# 780-00029_rev3_Pg3_Backplane_Instrument_.net
KiCad netlist of a schematic drawn in Altium Designer
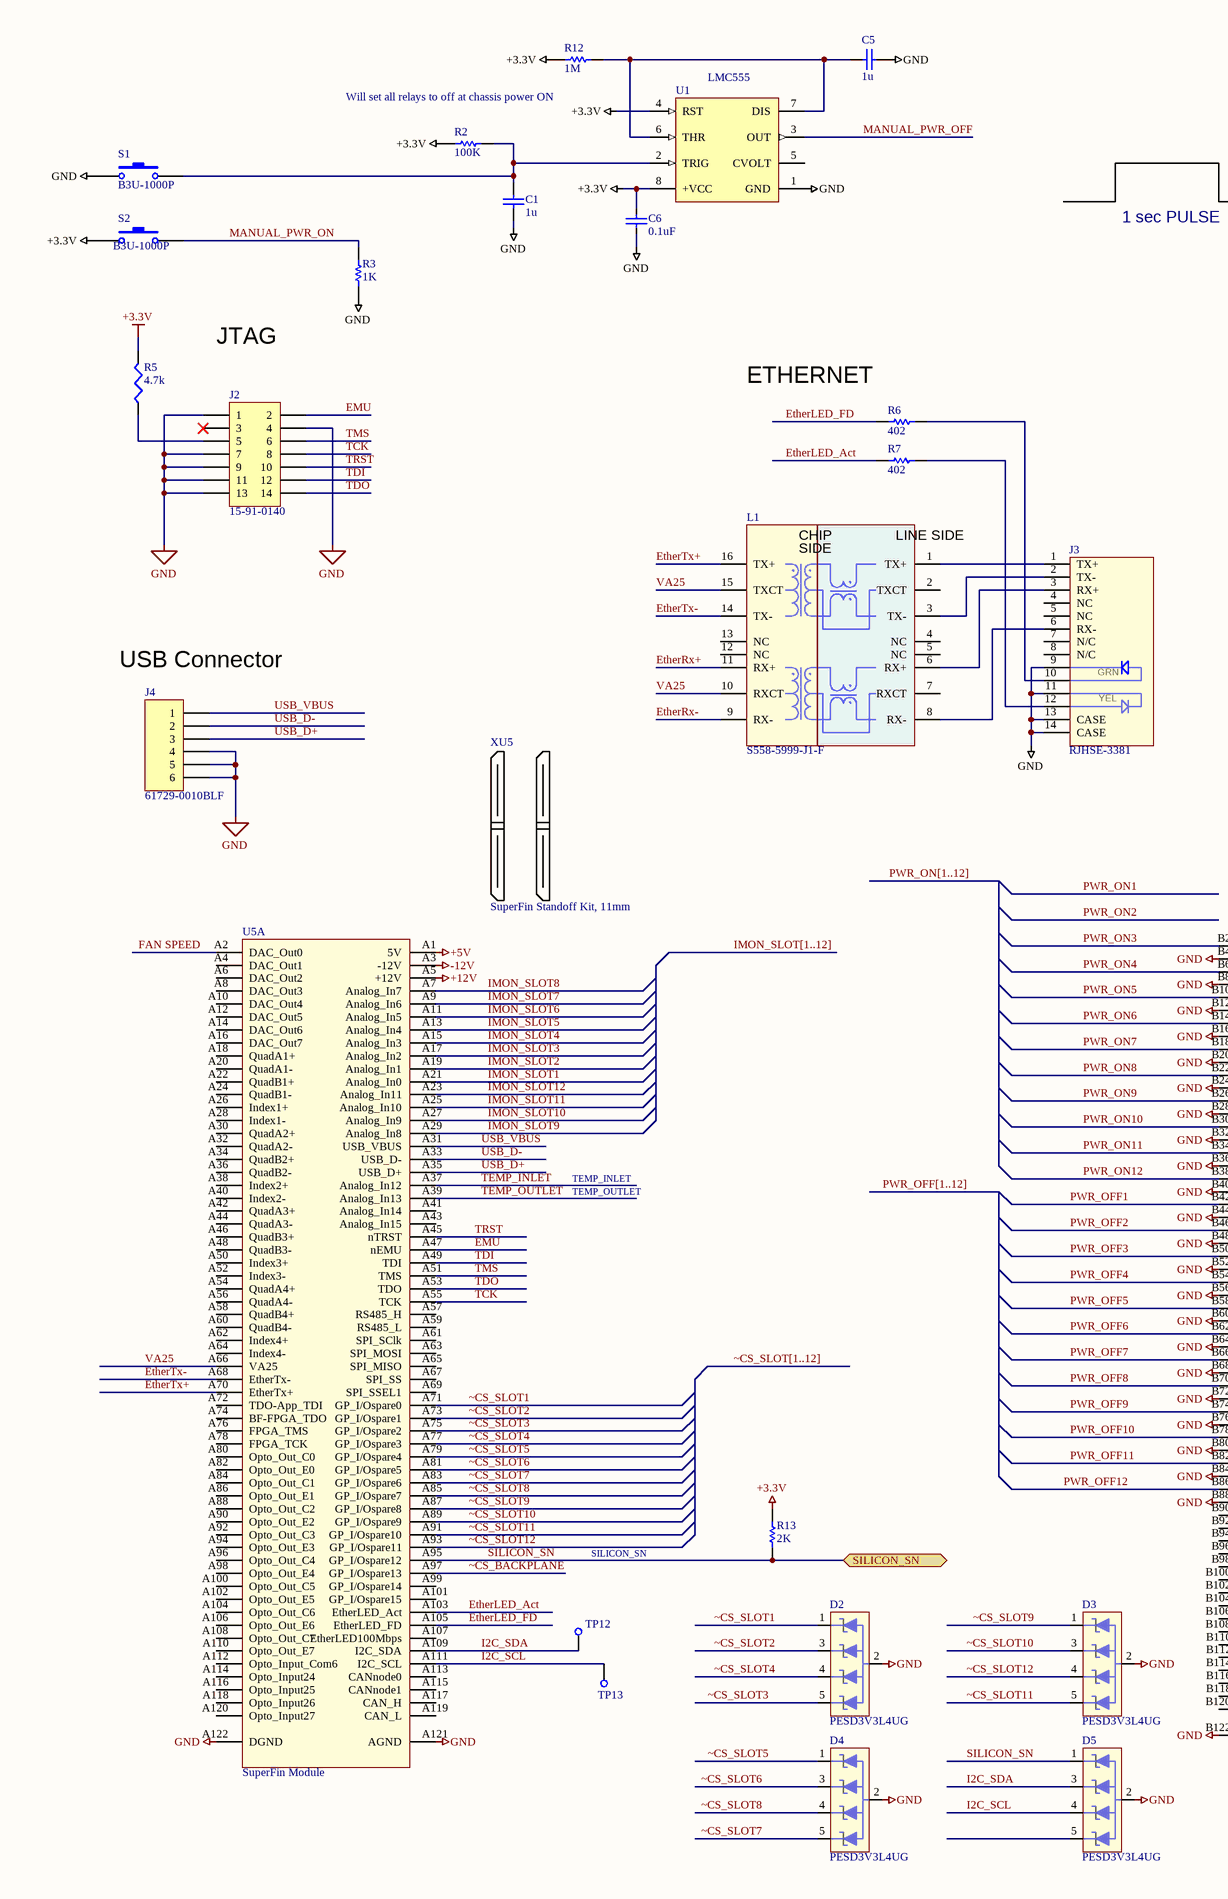
[diagram p0: 780-00029,rev3,Pg3,Backplane, Instrument Crate.SchDoc, left]
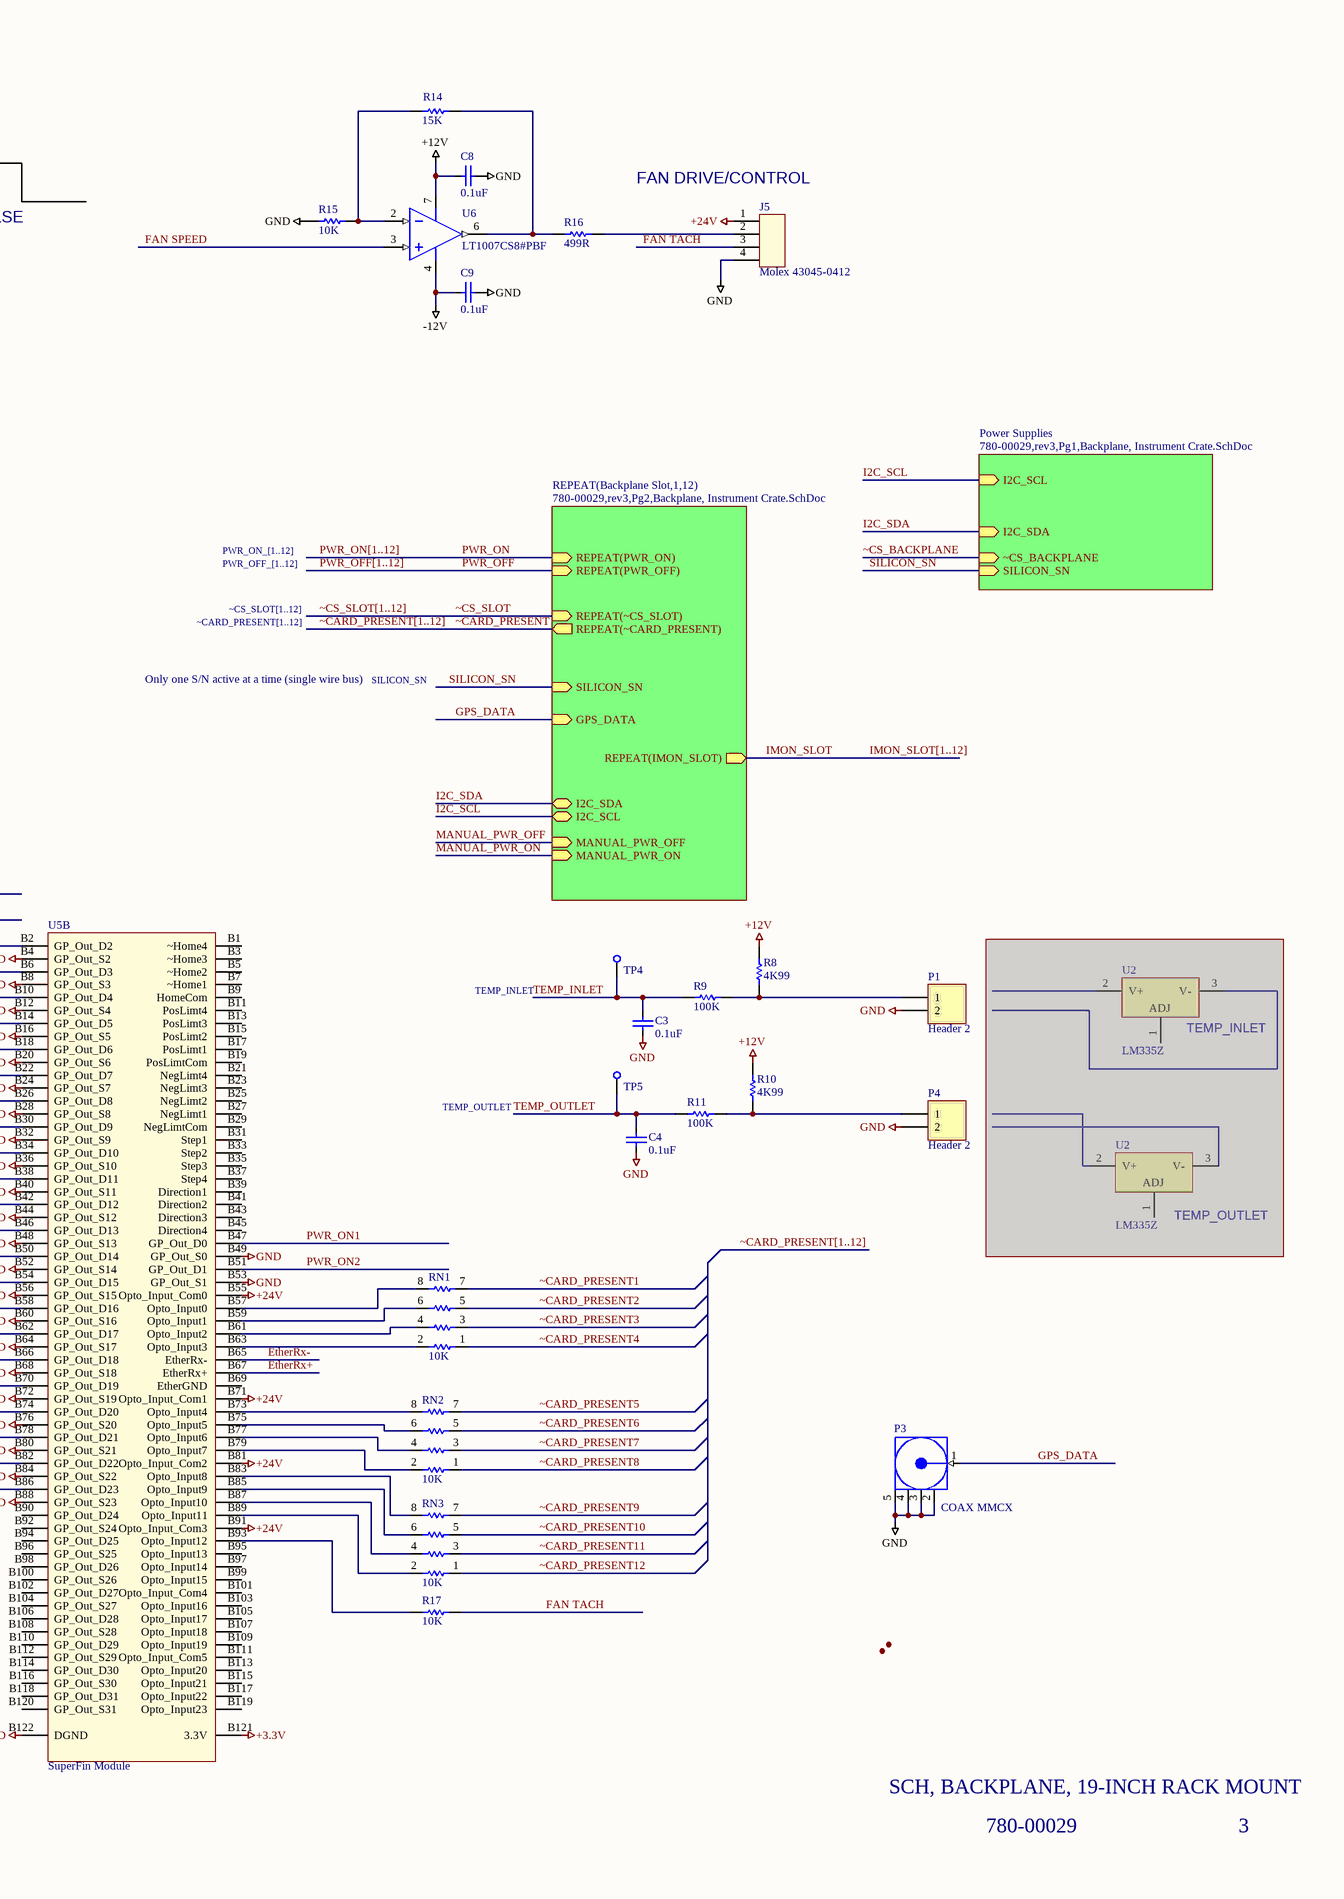
[diagram p1: 780-00029,rev3,Pg3,Backplane, Instrument Crate.SchDoc, right]

(export (version "E")
  (design (tool "Eeschema 10.0.6"))
  (components
    (comp (ref "C1")
      (value "1u")
      (footprint "2012[0805]")
      (description "Capacitor")
      (fields (field (name "MANUFACTURER") "Taiyo Yuden"))
      (libsource (lib "Miscellaneous Devices") (part "Cap"))
    )
    (comp (ref "C3")
      (value "0.1uF")
      (footprint "SMD_0805")
      (description "Capacitor")
      (fields (field (name "Comment") "Cap SMD"))
      (libsource (lib "Richs Schematic Components") (part "Cap SMD"))
    )
    (comp (ref "C4")
      (value "0.1uF")
      (footprint "SMD_0805")
      (description "Capacitor")
      (fields (field (name "Comment") "Cap SMD"))
      (libsource (lib "Richs Schematic Components") (part "Cap SMD"))
    )
    (comp (ref "C5")
      (value "1u")
      (footprint "SMD_0805")
      (description "Capacitor")
      (fields (field (name "MANUFACTURER") "Taiyo Yuden"))
      (libsource (lib "Miscellaneous Devices") (part "Cap"))
    )
    (comp (ref "C6")
      (value "0.1uF")
      (footprint "SMD_0805")
      (description "Capacitor")
      (fields (field (name "Comment") "Cap SMD"))
      (libsource (lib "Richs Schematic Components") (part "Cap SMD"))
    )
    (comp (ref "C8")
      (value "0.1uF")
      (footprint "SMD_0805")
      (description "Capacitor")
      (fields (field (name "Comment") "Cap SMD"))
      (libsource (lib "Richs Schematic Components") (part "Cap SMD"))
    )
    (comp (ref "C9")
      (value "0.1uF")
      (footprint "SMD_0805")
      (description "Capacitor")
      (fields (field (name "Comment") "Cap SMD"))
      (libsource (lib "Richs Schematic Components") (part "Cap SMD"))
    )
    (comp (ref "D2")
      (value "PESD3V3L4UG")
      (footprint "SOT-353")
      (description "Quad ESD Diode 3.3V")
      (fields (field (name "MANUFACTURER") "NXP"))
      (libsource (lib "Richs Schematic Components") (part "ESD Diode 3.3V Quad"))
    )
    (comp (ref "D3")
      (value "PESD3V3L4UG")
      (footprint "SOT-353")
      (description "Quad ESD Diode 3.3V")
      (fields (field (name "MANUFACTURER") "NXP"))
      (libsource (lib "Richs Schematic Components") (part "ESD Diode 3.3V Quad"))
    )
    (comp (ref "D4")
      (value "PESD3V3L4UG")
      (footprint "SOT-353")
      (description "Quad ESD Diode 3.3V")
      (fields (field (name "MANUFACTURER") "NXP"))
      (libsource (lib "Richs Schematic Components") (part "ESD Diode 3.3V Quad"))
    )
    (comp (ref "D5")
      (value "PESD3V3L4UG")
      (footprint "SOT-353")
      (description "Quad ESD Diode 3.3V")
      (fields (field (name "MANUFACTURER") "NXP"))
      (libsource (lib "Richs Schematic Components") (part "ESD Diode 3.3V Quad"))
    )
    (comp (ref "J2")
      (value "15-91-0140")
      (footprint "HDR2X7")
      (description "Header, 7-Pin, Dual row")
      (fields (field (name "MANUFACTURER") "Molex/Waldom"))
      (libsource (lib "Miscellaneous Connectors") (part "Header 7X2"))
    )
    (comp (ref "J3")
      (value "RJHSE-3381")
      (footprint "RJ45, VERT MOUNT, NO MAGNETICS")
      (description "Vertical PC mount, w/o magnetics")
      (libsource (lib "Richs Schematic Components") (part "CONN RJ-45 w/o magnetics"))
    )
    (comp (ref "J4")
      (value "61729-0010BLF")
      (footprint "USB Vertical PCB")
      (description "Header, 6-Pin")
      (fields (field (name "MANUFACTURER") "FCI"))
      (libsource (lib "Miscellaneous Connectors") (part "Header 6"))
    )
    (comp (ref "J5")
      (value "Molex 43045-0412")
      (footprint "CONN Molex Micro-fit, 4 POS")
      (description "Molex Micro Fit 3, Vert PC mount")
      (fields (field (name "MANUFACTURER") "Molex"))
      (libsource (lib "Richs Schematic Components") (part "CONN 4 pin 3mm"))
    )
    (comp (ref "L1")
      (value "S558-5999-J1-F")
      (footprint "10/100BT Magetics module")
      (description "10/100BT Magnetics Module")
      (libsource (lib "Richs Schematic Components") (part "Ethernet Magnetics module"))
    )
    (comp (ref "P1")
      (value "Header 2")
      (footprint "HDR1X2 for IDC")
      (description "Header, 2-Pin")
      (fields (field (name "MANUFACTURER") "TE Connectivity"))
      (libsource (lib "Richs Schematic Components") (part "Header 2"))
    )
    (comp (ref "P3")
      (value "COAX MMCX")
      (footprint "Miscellaneous Connectors:MMCX2.54-V5")
      (description "RF Coaxial PCB Connector, MMCX; Thru-Hole, Vertical Mount Plug,  50 Ohm Impedance")
      (fields (field (name "MANUFACTURER") "Emerson"))
      (libsource (lib "Richs Schematic Components") (part "COAX-M"))
    )
    (comp (ref "P4")
      (value "Header 2")
      (footprint "HDR1X2 for IDC")
      (description "Header, 2-Pin")
      (fields (field (name "MANUFACTURER") "TE Connectivity"))
      (libsource (lib "Richs Schematic Components") (part "Header 2"))
    )
    (comp (ref "R2")
      (value "100K")
      (footprint "SMD_0805")
      (description "Resistor 0805")
      (fields (field (name "MANUFACTURER") "Vishay/Dale") (field (name "Comment") "Res 0805"))
      (libsource (lib "Richs Schematic Components") (part "Res SMD"))
    )
    (comp (ref "R3")
      (value "1K")
      (footprint "SMD_0805")
      (description "Resistor 0805")
      (fields (field (name "MANUFACTURER") "Vishay/Dale") (field (name "Comment") "Res 0805"))
      (libsource (lib "Richs Schematic Components") (part "Res SMD"))
    )
    (comp (ref "R5")
      (value "4.7k")
      (footprint "2012[0805]")
      (description "Resistor")
      (fields (field (name "MANUFACTURER") "Dale/Vishay"))
      (libsource (lib "Miscellaneous Devices") (part "Res3"))
    )
    (comp (ref "R6")
      (value "402")
      (footprint "SMD_0805")
      (description "Resistor 0805")
      (fields (field (name "MANUFACTURER") "Vishay/Dale") (field (name "Comment") "Res 0805"))
      (libsource (lib "Richs Schematic Components") (part "Res SMD"))
    )
    (comp (ref "R7")
      (value "402")
      (footprint "SMD_0805")
      (description "Resistor 0805")
      (fields (field (name "MANUFACTURER") "Vishay/Dale") (field (name "Comment") "Res 0805"))
      (libsource (lib "Richs Schematic Components") (part "Res SMD"))
    )
    (comp (ref "R8")
      (value "4K99")
      (footprint "SMD_0805")
      (description "Resistor 0805")
      (fields (field (name "MANUFACTURER") "Vishay/Dale") (field (name "Comment") "Res 0805"))
      (libsource (lib "Richs Schematic Components") (part "Res SMD"))
    )
    (comp (ref "R9")
      (value "100K")
      (footprint "SMD_0805")
      (description "Resistor 0805")
      (fields (field (name "MANUFACTURER") "Vishay/Dale") (field (name "Comment") "Res 0805"))
      (libsource (lib "Richs Schematic Components") (part "Res SMD"))
    )
    (comp (ref "R10")
      (value "4K99")
      (footprint "SMD_0805")
      (description "Resistor 0805")
      (fields (field (name "MANUFACTURER") "Vishay/Dale") (field (name "Comment") "Res 0805"))
      (libsource (lib "Richs Schematic Components") (part "Res SMD"))
    )
    (comp (ref "R11")
      (value "100K")
      (footprint "SMD_0805")
      (description "Resistor 0805")
      (fields (field (name "MANUFACTURER") "Vishay/Dale") (field (name "Comment") "Res 0805"))
      (libsource (lib "Richs Schematic Components") (part "Res SMD"))
    )
    (comp (ref "R12")
      (value "1M")
      (footprint "SMD_0805")
      (description "Resistor 0805")
      (fields (field (name "MANUFACTURER") "Vishay/Dale") (field (name "Comment") "Res 0805"))
      (libsource (lib "Richs Schematic Components") (part "Res SMD"))
    )
    (comp (ref "R13")
      (value "2K")
      (footprint "SMD_0805")
      (description "Resistor 0805")
      (fields (field (name "MANUFACTURER") "Vishay/Dale") (field (name "Comment") "Res 0805"))
      (libsource (lib "Richs Schematic Components") (part "Res SMD"))
    )
    (comp (ref "R14")
      (value "15K")
      (footprint "SMD_0805")
      (description "Resistor 0805")
      (fields (field (name "MANUFACTURER") "Vishay/Dale") (field (name "Comment") "Res 0805"))
      (libsource (lib "Richs Schematic Components") (part "Res SMD"))
    )
    (comp (ref "R15")
      (value "10K")
      (footprint "SMD_0805")
      (description "Resistor 0805")
      (fields (field (name "MANUFACTURER") "Vishay/Dale") (field (name "Comment") "Res 0805"))
      (libsource (lib "Richs Schematic Components") (part "Res SMD"))
    )
    (comp (ref "R16")
      (value "499R")
      (footprint "SMD_0805")
      (description "Resistor 0805")
      (fields (field (name "MANUFACTURER") "Vishay/Dale") (field (name "Comment") "Res 0805"))
      (libsource (lib "Richs Schematic Components") (part "Res SMD"))
    )
    (comp (ref "R17")
      (value "10K")
      (footprint "SMD_0805")
      (description "Resistor 0805")
      (fields (field (name "MANUFACTURER") "Vishay/Dale") (field (name "Comment") "Res 0805"))
      (libsource (lib "Richs Schematic Components") (part "Res SMD"))
    )
    (comp (ref "RN1")
      (value "10K")
      (footprint "RES ARRAY 0603 x 4")
      (description "Resistor Array 4 Isolated")
      (fields (field (name "MANUFACTURER") "PANASONIC - ECG") (field (name "Comment") "RES ARRAY  x4 10K"))
      (libsource (lib "Richs Schematic Components") (part "RES ARRAY  x4 10K"))
    )
    (comp (ref "RN2")
      (value "10K")
      (footprint "RES ARRAY 0603 x 4")
      (description "Resistor Array 4 Isolated")
      (fields (field (name "MANUFACTURER") "PANASONIC - ECG") (field (name "Comment") "RES ARRAY  x4 10K"))
      (libsource (lib "Richs Schematic Components") (part "RES ARRAY  x4 10K"))
    )
    (comp (ref "RN3")
      (value "10K")
      (footprint "RES ARRAY 0603 x 4")
      (description "Resistor Array 4 Isolated")
      (fields (field (name "MANUFACTURER") "PANASONIC - ECG") (field (name "Comment") "RES ARRAY  x4 10K"))
      (libsource (lib "Richs Schematic Components") (part "RES ARRAY  x4 10K"))
    )
    (comp (ref "S1")
      (value "B3U-1000P")
      (footprint "B3U-1000P")
      (description "Switch")
      (fields (field (name "MANUFACTURER") "Omron Electronics"))
      (libsource (lib "Miscellaneous Devices") (part "SW-PB"))
    )
    (comp (ref "S2")
      (value "B3U-1000P")
      (footprint "B3U-1000P")
      (description "Switch")
      (fields (field (name "MANUFACTURER") "Omron Electronics"))
      (libsource (lib "Miscellaneous Devices") (part "SW-PB"))
    )
    (comp (ref "TP4")
      (value "Test Point SMD")
      (footprint "SMD_TEST POINT")
      (description "SMD loop test point")
      (libsource (lib "Richs Schematic Components") (part "Test Point SMD"))
    )
    (comp (ref "TP5")
      (value "Test Point SMD")
      (footprint "SMD_TEST POINT")
      (description "SMD loop test point")
      (libsource (lib "Richs Schematic Components") (part "Test Point SMD"))
    )
    (comp (ref "TP12")
      (value "Test Point SMD")
      (footprint "SMD_TEST POINT")
      (description "SMD loop test point")
      (libsource (lib "Richs Schematic Components") (part "Test Point SMD"))
    )
    (comp (ref "TP13")
      (value "Test Point SMD")
      (footprint "SMD_TEST POINT")
      (description "SMD loop test point")
      (libsource (lib "Richs Schematic Components") (part "Test Point SMD"))
    )
    (comp (ref "U1")
      (value "LMC555")
      (footprint "M08A_M")
      (description "Timer")
      (fields (field (name "MANUFACTURER") "National Semiconductor") (field (name "Comment") "LM555CMX"))
      (libsource (lib "NSC Analog") (part "LM555CMX"))
    )
    (comp (ref "U2")
      (value "LM335Z")
      (footprint "Z03A")
      (description "Precision Temperature Sensor")
      (fields (field (name "MANUFACTURER") "National Semiconductor"))
      (libsource (lib "NSC Temperature Sensor") (part "LM335Z"))
    )
    (comp (ref "U5")
      (value "SuperFin Module")
      (footprint "SuperFin Footprint")
      (libsource (lib "Richs Schematic Components") (part "SuperFin Module"))
    )
    (comp (ref "U6")
      (value "LT1007CS8#PBF")
      (footprint "S8_M")
      (description "Low Noise BJT input opamp")
      (fields (field (name "MANUFACTURER") "Linear Tech"))
      (libsource (lib "Richs Schematic Components") (part "LT1007CS8#PBF"))
    )
    (comp (ref "XU5")
      (value "SuperFin Standoff Kit, 11mm")
      (libsource (lib "Richs Schematic Components") (part "SuperFin Standoff Kit, 11mm"))
    )
  )
  (nets
    (net (code "1") (name "+3.3V") (class "Default")
      (node (ref "C6") (pin "2") (pinfunction "2_2") (pintype "passive"))
      (node (ref "R12") (pin "1") (pinfunction "1_1") (pintype "passive"))
      (node (ref "R13") (pin "2") (pinfunction "2_2") (pintype "passive"))
      (node (ref "R2") (pin "2") (pinfunction "2_2") (pintype "passive"))
      (node (ref "R5") (pin "2") (pinfunction "2_2") (pintype "passive"))
      (node (ref "S2") (pin "1") (pinfunction "1_1") (pintype "passive"))
      (node (ref "U1") (pin "4") (pinfunction "RST_4") (pintype "input"))
      (node (ref "U1") (pin "8") (pinfunction "+VCC_8") (pintype "power_in"))
      (node (ref "U5") (pin "B121") (pinfunction "3.3V_B121") (pintype "passive"))
    )
    (net (code "2") (name "+5V") (class "Default")
      (node (ref "U5") (pin "A1") (pinfunction "5V_A1") (pintype "passive"))
    )
    (net (code "3") (name "+12V") (class "Default")
      (node (ref "C8") (pin "1") (pinfunction "1_1") (pintype "passive"))
      (node (ref "R10") (pin "2") (pinfunction "2_2") (pintype "passive"))
      (node (ref "R8") (pin "2") (pinfunction "2_2") (pintype "passive"))
      (node (ref "U5") (pin "A5") (pinfunction "+12V_A5") (pintype "passive"))
      (node (ref "U6") (pin "7") (pinfunction "V+_7") (pintype "power_in"))
    )
    (net (code "4") (name "+24V") (class "Default")
      (node (ref "J5") (pin "1") (pintype "passive"))
      (node (ref "U5") (pin "B55") (pinfunction "Opto_Input_Com0_B55") (pintype "passive"))
      (node (ref "U5") (pin "B71") (pinfunction "Opto_Input_Com1_B71") (pintype "passive"))
      (node (ref "U5") (pin "B81") (pinfunction "Opto_Input_Com2_B81") (pintype "passive"))
      (node (ref "U5") (pin "B91") (pinfunction "Opto_Input_Com3_B91") (pintype "passive"))
    )
    (net (code "5") (name "-12V") (class "Default")
      (node (ref "C9") (pin "1") (pinfunction "1_1") (pintype "passive"))
      (node (ref "U5") (pin "A3") (pinfunction "-12V_A3") (pintype "passive"))
      (node (ref "U6") (pin "4") (pinfunction "V-_4") (pintype "power_in"))
    )
    (net (code "6") (name "/EMU") (class "Default")
      (node (ref "J2") (pin "2") (pinfunction "2_2") (pintype "passive"))
      (node (ref "U5") (pin "A47") (pinfunction "nEMU_A47") (pintype "passive"))
    )
    (net (code "7") (name "/EtherLED_Act") (class "Default")
      (node (ref "R7") (pin "1") (pinfunction "1_1") (pintype "passive"))
      (node (ref "U5") (pin "A103") (pinfunction "EtherLED_Act_A103") (pintype "passive"))
    )
    (net (code "8") (name "/EtherLED_FD") (class "Default")
      (node (ref "R6") (pin "1") (pinfunction "1_1") (pintype "passive"))
      (node (ref "U5") (pin "A105") (pinfunction "EtherLED_FD_A105") (pintype "passive"))
    )
    (net (code "9") (name "/EtherRx+") (class "Default")
      (node (ref "L1") (pin "11") (pinfunction "RX+_11") (pintype "passive"))
      (node (ref "U5") (pin "B67") (pinfunction "EtherRx+_B67") (pintype "passive"))
    )
    (net (code "10") (name "/EtherRx-") (class "Default")
      (node (ref "L1") (pin "9") (pinfunction "RX-_9") (pintype "passive"))
      (node (ref "U5") (pin "B65") (pinfunction "EtherRx-_B65") (pintype "passive"))
    )
    (net (code "11") (name "/EtherTx+") (class "Default")
      (node (ref "L1") (pin "16") (pinfunction "TX+_16") (pintype "passive"))
      (node (ref "U5") (pin "A70") (pinfunction "EtherTx+_A70") (pintype "passive"))
    )
    (net (code "12") (name "/EtherTx-") (class "Default")
      (node (ref "L1") (pin "14") (pinfunction "TX-_14") (pintype "passive"))
      (node (ref "U5") (pin "A68") (pinfunction "EtherTx-_A68") (pintype "passive"))
    )
    (net (code "13") (name "/FAN SPEED") (class "Default")
      (node (ref "U5") (pin "A2") (pinfunction "DAC_Out0_A2") (pintype "passive"))
      (node (ref "U6") (pin "3") (pinfunction "IN+_3") (pintype "input"))
    )
    (net (code "14") (name "/FAN TACH") (class "Default")
      (node (ref "J5") (pin "3") (pintype "passive"))
      (node (ref "R17") (pin "2") (pinfunction "2_2") (pintype "passive"))
    )
    (net (code "15") (name "/GPS_DATA") (class "Default")
      (node (ref "P3") (pin "1") (pinfunction "Signal_1") (pintype "input"))
    )
    (net (code "16") (name "/I2C_SCL") (class "Default")
      (node (ref "D5") (pin "4") (pintype "passive"))
      (node (ref "TP13") (pin "1") (pinfunction "TP_1") (pintype "passive"))
      (node (ref "U5") (pin "A111") (pinfunction "I2C_SCL_A111") (pintype "passive"))
    )
    (net (code "17") (name "/I2C_SDA") (class "Default")
      (node (ref "D5") (pin "3") (pintype "passive"))
      (node (ref "TP12") (pin "1") (pinfunction "TP_1") (pintype "passive"))
      (node (ref "U5") (pin "A109") (pinfunction "I2C_SDA_A109") (pintype "passive"))
    )
    (net (code "19") (name "/IMON_SLOT1") (class "Default")
      (node (ref "U5") (pin "A21") (pinfunction "Analog_In0_A21") (pintype "passive"))
    )
    (net (code "20") (name "/IMON_SLOT2") (class "Default")
      (node (ref "U5") (pin "A19") (pinfunction "Analog_In1_A19") (pintype "passive"))
    )
    (net (code "21") (name "/IMON_SLOT3") (class "Default")
      (node (ref "U5") (pin "A17") (pinfunction "Analog_In2_A17") (pintype "passive"))
    )
    (net (code "22") (name "/IMON_SLOT4") (class "Default")
      (node (ref "U5") (pin "A15") (pinfunction "Analog_In3_A15") (pintype "passive"))
    )
    (net (code "23") (name "/IMON_SLOT5") (class "Default")
      (node (ref "U5") (pin "A13") (pinfunction "Analog_In4_A13") (pintype "passive"))
    )
    (net (code "24") (name "/IMON_SLOT6") (class "Default")
      (node (ref "U5") (pin "A11") (pinfunction "Analog_In5_A11") (pintype "passive"))
    )
    (net (code "25") (name "/IMON_SLOT7") (class "Default")
      (node (ref "U5") (pin "A9") (pinfunction "Analog_In6_A9") (pintype "passive"))
    )
    (net (code "26") (name "/IMON_SLOT8") (class "Default")
      (node (ref "U5") (pin "A7") (pinfunction "Analog_In7_A7") (pintype "passive"))
    )
    (net (code "27") (name "/IMON_SLOT9") (class "Default")
      (node (ref "U5") (pin "A29") (pinfunction "Analog_In8_A29") (pintype "passive"))
    )
    (net (code "28") (name "/IMON_SLOT10") (class "Default")
      (node (ref "U5") (pin "A27") (pinfunction "Analog_In9_A27") (pintype "passive"))
    )
    (net (code "29") (name "/IMON_SLOT11") (class "Default")
      (node (ref "U5") (pin "A25") (pinfunction "Analog_In10_A25") (pintype "passive"))
    )
    (net (code "30") (name "/IMON_SLOT12") (class "Default")
      (node (ref "U5") (pin "A23") (pinfunction "Analog_In11_A23") (pintype "passive"))
    )
    (net (code "32") (name "/MANUAL_PWR_OFF") (class "Default")
      (node (ref "U1") (pin "3") (pinfunction "OUT_3") (pintype "output"))
    )
    (net (code "33") (name "/MANUAL_PWR_ON") (class "Default")
      (node (ref "R3") (pin "2") (pinfunction "2_2") (pintype "passive"))
      (node (ref "S2") (pin "2") (pinfunction "2_2") (pintype "passive"))
    )
    (net (code "35") (name "/PWR_OFF1") (class "Default")
      (node (ref "U5") (pin "B42") (pinfunction "GP_Out_D12_B42") (pintype "passive"))
    )
    (net (code "36") (name "/PWR_OFF2") (class "Default")
      (node (ref "U5") (pin "B46") (pinfunction "GP_Out_D13_B46") (pintype "passive"))
    )
    (net (code "37") (name "/PWR_OFF3") (class "Default")
      (node (ref "U5") (pin "B50") (pinfunction "GP_Out_D14_B50") (pintype "passive"))
    )
    (net (code "38") (name "/PWR_OFF4") (class "Default")
      (node (ref "U5") (pin "B54") (pinfunction "GP_Out_D15_B54") (pintype "passive"))
    )
    (net (code "39") (name "/PWR_OFF5") (class "Default")
      (node (ref "U5") (pin "B58") (pinfunction "GP_Out_D16_B58") (pintype "passive"))
    )
    (net (code "40") (name "/PWR_OFF6") (class "Default")
      (node (ref "U5") (pin "B62") (pinfunction "GP_Out_D17_B62") (pintype "passive"))
    )
    (net (code "41") (name "/PWR_OFF7") (class "Default")
      (node (ref "U5") (pin "B66") (pinfunction "GP_Out_D18_B66") (pintype "passive"))
    )
    (net (code "42") (name "/PWR_OFF8") (class "Default")
      (node (ref "U5") (pin "B70") (pinfunction "GP_Out_D19_B70") (pintype "passive"))
    )
    (net (code "43") (name "/PWR_OFF9") (class "Default")
      (node (ref "U5") (pin "B74") (pinfunction "GP_Out_D20_B74") (pintype "passive"))
    )
    (net (code "44") (name "/PWR_OFF10") (class "Default")
      (node (ref "U5") (pin "B78") (pinfunction "GP_Out_D21_B78") (pintype "passive"))
    )
    (net (code "45") (name "/PWR_OFF11") (class "Default")
      (node (ref "U5") (pin "B82") (pinfunction "GP_Out_D22_B82") (pintype "passive"))
    )
    (net (code "46") (name "/PWR_OFF12") (class "Default")
      (node (ref "U5") (pin "B86") (pinfunction "GP_Out_D23_B86") (pintype "passive"))
    )
    (net (code "49") (name "/PWR_ON1") (class "Default")
      (node (ref "U5") (pin "B47") (pinfunction "GP_Out_D0_B47") (pintype "passive"))
    )
    (net (code "50") (name "/PWR_ON2") (class "Default")
      (node (ref "U5") (pin "B51") (pinfunction "GP_Out_D1_B51") (pintype "passive"))
    )
    (net (code "51") (name "/PWR_ON3") (class "Default")
      (node (ref "U5") (pin "B2") (pinfunction "GP_Out_D2_B2") (pintype "passive"))
    )
    (net (code "52") (name "/PWR_ON4") (class "Default")
      (node (ref "U5") (pin "B6") (pinfunction "GP_Out_D3_B6") (pintype "passive"))
    )
    (net (code "53") (name "/PWR_ON5") (class "Default")
      (node (ref "U5") (pin "B10") (pinfunction "GP_Out_D4_B10") (pintype "passive"))
    )
    (net (code "54") (name "/PWR_ON6") (class "Default")
      (node (ref "U5") (pin "B14") (pinfunction "GP_Out_D5_B14") (pintype "passive"))
    )
    (net (code "55") (name "/PWR_ON7") (class "Default")
      (node (ref "U5") (pin "B18") (pinfunction "GP_Out_D6_B18") (pintype "passive"))
    )
    (net (code "56") (name "/PWR_ON8") (class "Default")
      (node (ref "U5") (pin "B22") (pinfunction "GP_Out_D7_B22") (pintype "passive"))
    )
    (net (code "57") (name "/PWR_ON9") (class "Default")
      (node (ref "U5") (pin "B26") (pinfunction "GP_Out_D8_B26") (pintype "passive"))
    )
    (net (code "58") (name "/PWR_ON10") (class "Default")
      (node (ref "U5") (pin "B30") (pinfunction "GP_Out_D9_B30") (pintype "passive"))
    )
    (net (code "59") (name "/PWR_ON11") (class "Default")
      (node (ref "U5") (pin "B34") (pinfunction "GP_Out_D10_B34") (pintype "passive"))
    )
    (net (code "60") (name "/PWR_ON12") (class "Default")
      (node (ref "U5") (pin "B38") (pinfunction "GP_Out_D11_B38") (pintype "passive"))
    )
    (net (code "62") (name "/SILICON_SN") (class "Default")
      (node (ref "D5") (pin "1") (pintype "passive"))
      (node (ref "R13") (pin "1") (pinfunction "1_1") (pintype "passive"))
      (node (ref "U5") (pin "A95") (pinfunction "GP_I/Ospare12_A95") (pintype "passive"))
    )
    (net (code "63") (name "/TCK") (class "Default")
      (node (ref "J2") (pin "8") (pinfunction "8_8") (pintype "passive"))
      (node (ref "U5") (pin "A55") (pinfunction "TCK_A55") (pintype "passive"))
    )
    (net (code "64") (name "/TDI") (class "Default")
      (node (ref "J2") (pin "12") (pinfunction "12_12") (pintype "passive"))
      (node (ref "U5") (pin "A49") (pinfunction "TDI_A49") (pintype "passive"))
    )
    (net (code "65") (name "/TDO") (class "Default")
      (node (ref "J2") (pin "14") (pinfunction "14_14") (pintype "passive"))
      (node (ref "U5") (pin "A53") (pinfunction "TDO_A53") (pintype "passive"))
    )
    (net (code "66") (name "/TEMP_INLET") (class "Default")
      (node (ref "C3") (pin "2") (pinfunction "2_2") (pintype "passive"))
      (node (ref "R9") (pin "1") (pinfunction "1_1") (pintype "passive"))
      (node (ref "TP4") (pin "1") (pinfunction "TP_1") (pintype "passive"))
      (node (ref "U5") (pin "A37") (pinfunction "Analog_In12_A37") (pintype "passive"))
    )
    (net (code "67") (name "/TEMP_OUTLET") (class "Default")
      (node (ref "C4") (pin "2") (pinfunction "2_2") (pintype "passive"))
      (node (ref "R11") (pin "1") (pinfunction "1_1") (pintype "passive"))
      (node (ref "TP5") (pin "1") (pinfunction "TP_1") (pintype "passive"))
      (node (ref "U5") (pin "A39") (pinfunction "Analog_In13_A39") (pintype "passive"))
    )
    (net (code "68") (name "/TMS") (class "Default")
      (node (ref "J2") (pin "6") (pinfunction "6_6") (pintype "passive"))
      (node (ref "U5") (pin "A51") (pinfunction "TMS_A51") (pintype "passive"))
    )
    (net (code "69") (name "/TRST") (class "Default")
      (node (ref "J2") (pin "10") (pinfunction "10_10") (pintype "passive"))
      (node (ref "U5") (pin "A45") (pinfunction "nTRST_A45") (pintype "passive"))
    )
    (net (code "70") (name "/USB_D+") (class "Default")
      (node (ref "J4") (pin "3") (pinfunction "3_3") (pintype "passive"))
      (node (ref "U5") (pin "A35") (pinfunction "USB_D+_A35") (pintype "passive"))
    )
    (net (code "71") (name "/USB_D-") (class "Default")
      (node (ref "J4") (pin "2") (pinfunction "2_2") (pintype "passive"))
      (node (ref "U5") (pin "A33") (pinfunction "USB_D-_A33") (pintype "passive"))
    )
    (net (code "72") (name "/USB_VBUS") (class "Default")
      (node (ref "J4") (pin "1") (pinfunction "1_1") (pintype "passive"))
      (node (ref "U5") (pin "A31") (pinfunction "USB_VBUS_A31") (pintype "passive"))
    )
    (net (code "73") (name "/VA25") (class "Default")
      (node (ref "L1") (pin "10") (pinfunction "RXCT_10") (pintype "passive"))
      (node (ref "L1") (pin "15") (pinfunction "TXCT_15") (pintype "passive"))
      (node (ref "U5") (pin "A66") (pinfunction "VA25_A66") (pintype "passive"))
    )
    (net (code "75") (name "/~CARD_PRESENT1") (class "Default")
      (node (ref "RN1") (pin "7") (pinfunction "1_7") (pintype "passive"))
    )
    (net (code "76") (name "/~CARD_PRESENT2") (class "Default")
      (node (ref "RN1") (pin "5") (pinfunction "5_5") (pintype "passive"))
    )
    (net (code "77") (name "/~CARD_PRESENT3") (class "Default")
      (node (ref "RN1") (pin "3") (pinfunction "3_3") (pintype "passive"))
    )
    (net (code "78") (name "/~CARD_PRESENT4") (class "Default")
      (node (ref "RN1") (pin "1") (pinfunction "1_1") (pintype "passive"))
    )
    (net (code "79") (name "/~CARD_PRESENT5") (class "Default")
      (node (ref "RN2") (pin "7") (pinfunction "1_7") (pintype "passive"))
    )
    (net (code "80") (name "/~CARD_PRESENT6") (class "Default")
      (node (ref "RN2") (pin "5") (pinfunction "5_5") (pintype "passive"))
    )
    (net (code "81") (name "/~CARD_PRESENT7") (class "Default")
      (node (ref "RN2") (pin "3") (pinfunction "3_3") (pintype "passive"))
    )
    (net (code "82") (name "/~CARD_PRESENT8") (class "Default")
      (node (ref "RN2") (pin "1") (pinfunction "1_1") (pintype "passive"))
    )
    (net (code "83") (name "/~CARD_PRESENT9") (class "Default")
      (node (ref "RN3") (pin "7") (pinfunction "1_7") (pintype "passive"))
    )
    (net (code "84") (name "/~CARD_PRESENT10") (class "Default")
      (node (ref "RN3") (pin "5") (pinfunction "5_5") (pintype "passive"))
    )
    (net (code "85") (name "/~CARD_PRESENT11") (class "Default")
      (node (ref "RN3") (pin "3") (pinfunction "3_3") (pintype "passive"))
    )
    (net (code "86") (name "/~CARD_PRESENT12") (class "Default")
      (node (ref "RN3") (pin "1") (pinfunction "1_1") (pintype "passive"))
    )
    (net (code "88") (name "/~CS_BACKPLANE") (class "Default")
      (node (ref "U5") (pin "A97") (pinfunction "GP_I/Ospare13_A97") (pintype "passive"))
    )
    (net (code "90") (name "/~CS_SLOT1") (class "Default")
      (node (ref "D2") (pin "1") (pintype "passive"))
      (node (ref "U5") (pin "A71") (pinfunction "GP_I/Ospare0_A71") (pintype "passive"))
    )
    (net (code "91") (name "/~CS_SLOT2") (class "Default")
      (node (ref "D2") (pin "3") (pintype "passive"))
      (node (ref "U5") (pin "A73") (pinfunction "GP_I/Ospare1_A73") (pintype "passive"))
    )
    (net (code "92") (name "/~CS_SLOT3") (class "Default")
      (node (ref "D2") (pin "5") (pintype "passive"))
      (node (ref "U5") (pin "A75") (pinfunction "GP_I/Ospare2_A75") (pintype "passive"))
    )
    (net (code "93") (name "/~CS_SLOT4") (class "Default")
      (node (ref "D2") (pin "4") (pintype "passive"))
      (node (ref "U5") (pin "A77") (pinfunction "GP_I/Ospare3_A77") (pintype "passive"))
    )
    (net (code "94") (name "/~CS_SLOT5") (class "Default")
      (node (ref "D4") (pin "1") (pintype "passive"))
      (node (ref "U5") (pin "A79") (pinfunction "GP_I/Ospare4_A79") (pintype "passive"))
    )
    (net (code "95") (name "/~CS_SLOT6") (class "Default")
      (node (ref "D4") (pin "3") (pintype "passive"))
      (node (ref "U5") (pin "A81") (pinfunction "GP_I/Ospare5_A81") (pintype "passive"))
    )
    (net (code "96") (name "/~CS_SLOT7") (class "Default")
      (node (ref "D4") (pin "5") (pintype "passive"))
      (node (ref "U5") (pin "A83") (pinfunction "GP_I/Ospare6_A83") (pintype "passive"))
    )
    (net (code "97") (name "/~CS_SLOT8") (class "Default")
      (node (ref "D4") (pin "4") (pintype "passive"))
      (node (ref "U5") (pin "A85") (pinfunction "GP_I/Ospare7_A85") (pintype "passive"))
    )
    (net (code "98") (name "/~CS_SLOT9") (class "Default")
      (node (ref "D3") (pin "1") (pintype "passive"))
      (node (ref "U5") (pin "A87") (pinfunction "GP_I/Ospare8_A87") (pintype "passive"))
    )
    (net (code "99") (name "/~CS_SLOT10") (class "Default")
      (node (ref "D3") (pin "3") (pintype "passive"))
      (node (ref "U5") (pin "A89") (pinfunction "GP_I/Ospare9_A89") (pintype "passive"))
    )
    (net (code "100") (name "/~CS_SLOT11") (class "Default")
      (node (ref "D3") (pin "5") (pintype "passive"))
      (node (ref "U5") (pin "A91") (pinfunction "GP_I/Ospare10_A91") (pintype "passive"))
    )
    (net (code "101") (name "/~CS_SLOT12") (class "Default")
      (node (ref "D3") (pin "4") (pintype "passive"))
      (node (ref "U5") (pin "A93") (pinfunction "GP_I/Ospare11_A93") (pintype "passive"))
    )
    (net (code "103") (name "GND") (class "Default")
      (node (ref "C1") (pin "1") (pinfunction "1_1") (pintype "passive"))
      (node (ref "C3") (pin "1") (pinfunction "1_1") (pintype "passive"))
      (node (ref "C4") (pin "1") (pinfunction "1_1") (pintype "passive"))
      (node (ref "C5") (pin "2") (pinfunction "2_2") (pintype "passive"))
      (node (ref "C6") (pin "1") (pinfunction "1_1") (pintype "passive"))
      (node (ref "C8") (pin "2") (pinfunction "2_2") (pintype "passive"))
      (node (ref "C9") (pin "2") (pinfunction "2_2") (pintype "passive"))
      (node (ref "D2") (pin "2") (pintype "passive"))
      (node (ref "D3") (pin "2") (pintype "passive"))
      (node (ref "D4") (pin "2") (pintype "passive"))
      (node (ref "D5") (pin "2") (pintype "passive"))
      (node (ref "J2") (pin "1") (pinfunction "1_1") (pintype "passive"))
      (node (ref "J2") (pin "11") (pinfunction "11_11") (pintype "passive"))
      (node (ref "J2") (pin "13") (pinfunction "13_13") (pintype "passive"))
      (node (ref "J2") (pin "4") (pinfunction "4_4") (pintype "passive"))
      (node (ref "J2") (pin "7") (pinfunction "7_7") (pintype "passive"))
      (node (ref "J2") (pin "9") (pinfunction "9_9") (pintype "passive"))
      (node (ref "J3") (pin "11") (pinfunction "YEL-Cathode_11") (pintype "passive"))
      (node (ref "J3") (pin "13") (pinfunction "CASE_13") (pintype "passive"))
      (node (ref "J3") (pin "14") (pinfunction "CASE_14") (pintype "passive"))
      (node (ref "J3") (pin "9") (pinfunction "GRN-Anode_9") (pintype "passive"))
      (node (ref "J4") (pin "4") (pinfunction "4_4") (pintype "passive"))
      (node (ref "J4") (pin "5") (pinfunction "5_5") (pintype "passive"))
      (node (ref "J4") (pin "6") (pinfunction "6_6") (pintype "passive"))
      (node (ref "J5") (pin "4") (pintype "passive"))
      (node (ref "P1") (pin "2") (pinfunction "2_2") (pintype "passive"))
      (node (ref "P3") (pin "2") (pinfunction "GND_2") (pintype "power_in"))
      (node (ref "P3") (pin "3") (pinfunction "GND_3") (pintype "power_in"))
      (node (ref "P3") (pin "4") (pinfunction "GND_4") (pintype "power_in"))
      (node (ref "P3") (pin "5") (pinfunction "GND_5") (pintype "power_in"))
      (node (ref "P4") (pin "2") (pinfunction "2_2") (pintype "passive"))
      (node (ref "R15") (pin "1") (pinfunction "1_1") (pintype "passive"))
      (node (ref "R3") (pin "1") (pinfunction "1_1") (pintype "passive"))
      (node (ref "S1") (pin "1") (pinfunction "1_1") (pintype "passive"))
      (node (ref "U1") (pin "1") (pinfunction "GND_1") (pintype "power_in"))
      (node (ref "U5") (pin "A121") (pinfunction "AGND_A121") (pintype "passive"))
      (node (ref "U5") (pin "A122") (pinfunction "DGND_A122") (pintype "passive"))
      (node (ref "U5") (pin "B12") (pinfunction "GP_Out_S4_B12") (pintype "passive"))
      (node (ref "U5") (pin "B122") (pinfunction "DGND_B122") (pintype "passive"))
      (node (ref "U5") (pin "B16") (pinfunction "GP_Out_S5_B16") (pintype "passive"))
      (node (ref "U5") (pin "B20") (pinfunction "GP_Out_S6_B20") (pintype "passive"))
      (node (ref "U5") (pin "B24") (pinfunction "GP_Out_S7_B24") (pintype "passive"))
      (node (ref "U5") (pin "B28") (pinfunction "GP_Out_S8_B28") (pintype "passive"))
      (node (ref "U5") (pin "B32") (pinfunction "GP_Out_S9_B32") (pintype "passive"))
      (node (ref "U5") (pin "B36") (pinfunction "GP_Out_S10_B36") (pintype "passive"))
      (node (ref "U5") (pin "B4") (pinfunction "GP_Out_S2_B4") (pintype "passive"))
      (node (ref "U5") (pin "B40") (pinfunction "GP_Out_S11_B40") (pintype "passive"))
      (node (ref "U5") (pin "B44") (pinfunction "GP_Out_S12_B44") (pintype "passive"))
      (node (ref "U5") (pin "B48") (pinfunction "GP_Out_S13_B48") (pintype "passive"))
      (node (ref "U5") (pin "B49") (pinfunction "GP_Out_S0_B49") (pintype "passive"))
      (node (ref "U5") (pin "B52") (pinfunction "GP_Out_S14_B52") (pintype "passive"))
      (node (ref "U5") (pin "B53") (pinfunction "GP_Out_S1_B53") (pintype "passive"))
      (node (ref "U5") (pin "B56") (pinfunction "GP_Out_S15_B56") (pintype "passive"))
      (node (ref "U5") (pin "B60") (pinfunction "GP_Out_S16_B60") (pintype "passive"))
      (node (ref "U5") (pin "B64") (pinfunction "GP_Out_S17_B64") (pintype "passive"))
      (node (ref "U5") (pin "B68") (pinfunction "GP_Out_S18_B68") (pintype "passive"))
      (node (ref "U5") (pin "B72") (pinfunction "GP_Out_S19_B72") (pintype "passive"))
      (node (ref "U5") (pin "B76") (pinfunction "GP_Out_S20_B76") (pintype "passive"))
      (node (ref "U5") (pin "B8") (pinfunction "GP_Out_S3_B8") (pintype "passive"))
      (node (ref "U5") (pin "B80") (pinfunction "GP_Out_S21_B80") (pintype "passive"))
      (node (ref "U5") (pin "B84") (pinfunction "GP_Out_S22_B84") (pintype "passive"))
      (node (ref "U5") (pin "B88") (pinfunction "GP_Out_S23_B88") (pintype "passive"))
    )
    (net (code "104") (name "Net-(J2-Pad5)") (class "Default")
      (node (ref "J2") (pin "5") (pinfunction "5_5") (pintype "passive"))
      (node (ref "R5") (pin "1") (pinfunction "1_1") (pintype "passive"))
    )
    (net (code "105") (name "Net-(J3-GRN-Cathode)") (class "Default")
      (node (ref "J3") (pin "10") (pinfunction "GRN-Cathode_10") (pintype "passive"))
      (node (ref "R6") (pin "2") (pinfunction "2_2") (pintype "passive"))
    )
    (net (code "106") (name "Net-(J3-RX+)") (class "Default")
      (node (ref "J3") (pin "3") (pinfunction "RX+_3") (pintype "passive"))
      (node (ref "L1") (pin "6") (pinfunction "RX+_6") (pintype "passive"))
    )
    (net (code "107") (name "Net-(J3-RX-)") (class "Default")
      (node (ref "J3") (pin "6") (pinfunction "RX-_6") (pintype "passive"))
      (node (ref "L1") (pin "8") (pinfunction "RX-_8") (pintype "passive"))
    )
    (net (code "108") (name "Net-(J3-TX+)") (class "Default")
      (node (ref "J3") (pin "1") (pinfunction "TX+_1") (pintype "passive"))
      (node (ref "L1") (pin "1") (pinfunction "TX+_1") (pintype "passive"))
    )
    (net (code "109") (name "Net-(J3-TX-)") (class "Default")
      (node (ref "J3") (pin "2") (pinfunction "TX-_2") (pintype "passive"))
      (node (ref "L1") (pin "3") (pinfunction "TX-_3") (pintype "passive"))
    )
    (net (code "110") (name "Net-(J3-YEL-Anode)") (class "Default")
      (node (ref "J3") (pin "12") (pinfunction "YEL-Anode_12") (pintype "passive"))
      (node (ref "R7") (pin "2") (pinfunction "2_2") (pintype "passive"))
    )
    (net (code "111") (name "Net-(J5-Pad2)") (class "Default")
      (node (ref "J5") (pin "2") (pintype "passive"))
      (node (ref "R16") (pin "1") (pinfunction "1_1") (pintype "passive"))
    )
    (net (code "112") (name "Net-(P1-Pad1)") (class "Default")
      (node (ref "P1") (pin "1") (pinfunction "1_1") (pintype "passive"))
      (node (ref "R8") (pin "1") (pinfunction "1_1") (pintype "passive"))
      (node (ref "R9") (pin "2") (pinfunction "2_2") (pintype "passive"))
    )
    (net (code "113") (name "Net-(P4-Pad1)") (class "Default")
      (node (ref "P4") (pin "1") (pinfunction "1_1") (pintype "passive"))
      (node (ref "R10") (pin "1") (pinfunction "1_1") (pintype "passive"))
      (node (ref "R11") (pin "2") (pinfunction "2_2") (pintype "passive"))
    )
    (net (code "114") (name "Net-(U1-DIS)") (class "Default")
      (node (ref "C5") (pin "1") (pinfunction "1_1") (pintype "passive"))
      (node (ref "R12") (pin "2") (pinfunction "2_2") (pintype "passive"))
      (node (ref "U1") (pin "6") (pinfunction "THR_6") (pintype "input"))
      (node (ref "U1") (pin "7") (pinfunction "DIS_7") (pintype "open_collector"))
    )
    (net (code "115") (name "Net-(U1-TRIG)") (class "Default")
      (node (ref "C1") (pin "2") (pinfunction "2_2") (pintype "passive"))
      (node (ref "R2") (pin "1") (pinfunction "1_1") (pintype "passive"))
      (node (ref "S1") (pin "2") (pinfunction "2_2") (pintype "passive"))
      (node (ref "U1") (pin "2") (pinfunction "TRIG_2") (pintype "input"))
    )
    (net (code "116") (name "Net-(U5B-Opto_Input0)") (class "Default")
      (node (ref "RN1") (pin "8") (pinfunction "8_8") (pintype "passive"))
      (node (ref "U5") (pin "B57") (pinfunction "Opto_Input0_B57") (pintype "passive"))
    )
    (net (code "117") (name "Net-(U5B-Opto_Input1)") (class "Default")
      (node (ref "RN1") (pin "6") (pinfunction "6_6") (pintype "passive"))
      (node (ref "U5") (pin "B59") (pinfunction "Opto_Input1_B59") (pintype "passive"))
    )
    (net (code "118") (name "Net-(U5B-Opto_Input2)") (class "Default")
      (node (ref "RN1") (pin "4") (pinfunction "4_4") (pintype "passive"))
      (node (ref "U5") (pin "B61") (pinfunction "Opto_Input2_B61") (pintype "passive"))
    )
    (net (code "119") (name "Net-(U5B-Opto_Input3)") (class "Default")
      (node (ref "RN1") (pin "2") (pinfunction "2_2") (pintype "passive"))
      (node (ref "U5") (pin "B63") (pinfunction "Opto_Input3_B63") (pintype "passive"))
    )
    (net (code "120") (name "Net-(U5B-Opto_Input4)") (class "Default")
      (node (ref "RN2") (pin "8") (pinfunction "8_8") (pintype "passive"))
      (node (ref "U5") (pin "B73") (pinfunction "Opto_Input4_B73") (pintype "passive"))
    )
    (net (code "121") (name "Net-(U5B-Opto_Input5)") (class "Default")
      (node (ref "RN2") (pin "6") (pinfunction "6_6") (pintype "passive"))
      (node (ref "U5") (pin "B75") (pinfunction "Opto_Input5_B75") (pintype "passive"))
    )
    (net (code "122") (name "Net-(U5B-Opto_Input6)") (class "Default")
      (node (ref "RN2") (pin "4") (pinfunction "4_4") (pintype "passive"))
      (node (ref "U5") (pin "B77") (pinfunction "Opto_Input6_B77") (pintype "passive"))
    )
    (net (code "123") (name "Net-(U5B-Opto_Input7)") (class "Default")
      (node (ref "RN2") (pin "2") (pinfunction "2_2") (pintype "passive"))
      (node (ref "U5") (pin "B79") (pinfunction "Opto_Input7_B79") (pintype "passive"))
    )
    (net (code "124") (name "Net-(U5B-Opto_Input8)") (class "Default")
      (node (ref "RN3") (pin "8") (pinfunction "8_8") (pintype "passive"))
      (node (ref "U5") (pin "B83") (pinfunction "Opto_Input8_B83") (pintype "passive"))
    )
    (net (code "125") (name "Net-(U5B-Opto_Input9)") (class "Default")
      (node (ref "RN3") (pin "6") (pinfunction "6_6") (pintype "passive"))
      (node (ref "U5") (pin "B85") (pinfunction "Opto_Input9_B85") (pintype "passive"))
    )
    (net (code "126") (name "Net-(U5B-Opto_Input10)") (class "Default")
      (node (ref "RN3") (pin "4") (pinfunction "4_4") (pintype "passive"))
      (node (ref "U5") (pin "B87") (pinfunction "Opto_Input10_B87") (pintype "passive"))
    )
    (net (code "127") (name "Net-(U5B-Opto_Input11)") (class "Default")
      (node (ref "RN3") (pin "2") (pinfunction "2_2") (pintype "passive"))
      (node (ref "U5") (pin "B89") (pinfunction "Opto_Input11_B89") (pintype "passive"))
    )
    (net (code "128") (name "Net-(U5B-Opto_Input12)") (class "Default")
      (node (ref "R17") (pin "1") (pinfunction "1_1") (pintype "passive"))
      (node (ref "U5") (pin "B93") (pinfunction "Opto_Input12_B93") (pintype "passive"))
    )
    (net (code "129") (name "Net-(U6-IN-)") (class "Default")
      (node (ref "R14") (pin "1") (pinfunction "1_1") (pintype "passive"))
      (node (ref "R15") (pin "2") (pinfunction "2_2") (pintype "passive"))
      (node (ref "U6") (pin "2") (pinfunction "IN-_2") (pintype "input"))
    )
    (net (code "130") (name "Net-(U6-OUT)") (class "Default")
      (node (ref "R14") (pin "2") (pinfunction "2_2") (pintype "passive"))
      (node (ref "R16") (pin "2") (pinfunction "2_2") (pintype "passive"))
      (node (ref "U6") (pin "6") (pinfunction "OUT_6") (pintype "output"))
    )
    (net (code "131") (name "unconnected-(D5-Pad5)") (class "Default")
      (node (ref "D5") (pin "5") (pintype "passive"))
    )
    (net (code "132") (name "unconnected-(J2-Pad3)") (class "Default")
      (node (ref "J2") (pin "3") (pinfunction "3_3") (pintype "passive+no_connect"))
    )
    (net (code "133") (name "unconnected-(J3-NC-Pad4)") (class "Default")
      (node (ref "J3") (pin "4") (pinfunction "NC_4") (pintype "passive"))
    )
    (net (code "134") (name "unconnected-(J3-NC-Pad5)") (class "Default")
      (node (ref "J3") (pin "5") (pinfunction "NC_5") (pintype "passive"))
    )
    (net (code "135") (name "unconnected-(J3-N{slash}C-Pad7)") (class "Default")
      (node (ref "J3") (pin "7") (pinfunction "N/C_7") (pintype "passive"))
    )
    (net (code "136") (name "unconnected-(J3-N{slash}C-Pad8)") (class "Default")
      (node (ref "J3") (pin "8") (pinfunction "N/C_8") (pintype "passive"))
    )
    (net (code "137") (name "unconnected-(L1-NC-Pad4)") (class "Default")
      (node (ref "L1") (pin "4") (pinfunction "NC_4") (pintype "passive"))
    )
    (net (code "138") (name "unconnected-(L1-NC-Pad5)") (class "Default")
      (node (ref "L1") (pin "5") (pinfunction "NC_5") (pintype "passive"))
    )
    (net (code "139") (name "unconnected-(L1-NC-Pad12)") (class "Default")
      (node (ref "L1") (pin "12") (pinfunction "NC_12") (pintype "passive"))
    )
    (net (code "140") (name "unconnected-(L1-NC-Pad13)") (class "Default")
      (node (ref "L1") (pin "13") (pinfunction "NC_13") (pintype "passive"))
    )
    (net (code "141") (name "unconnected-(L1-RXCT-Pad7)") (class "Default")
      (node (ref "L1") (pin "7") (pinfunction "RXCT_7") (pintype "passive"))
    )
    (net (code "142") (name "unconnected-(L1-TXCT-Pad2)") (class "Default")
      (node (ref "L1") (pin "2") (pinfunction "TXCT_2") (pintype "passive"))
    )
    (net (code "143") (name "unconnected-(U1-CVOLT-Pad5)") (class "Default")
      (node (ref "U1") (pin "5") (pinfunction "CVOLT_5") (pintype "passive"))
    )
    (net (code "144") (name "unconnected-(U2-ADJ-Pad1)") (class "Default")
      (node (ref "U2") (pin "1") (pinfunction "ADJ_1") (pintype "passive"))
    )
    (net (code "145") (name "unconnected-(U2-ADJ-Pad1)_1") (class "Default")
      (node (ref "U2") (pin "1") (pinfunction "ADJ_1") (pintype "passive"))
    )
    (net (code "146") (name "unconnected-(U2-V+-Pad2)") (class "Default")
      (node (ref "U2") (pin "2") (pinfunction "V+_2") (pintype "passive"))
    )
    (net (code "147") (name "unconnected-(U2-V+-Pad2)_1") (class "Default")
      (node (ref "U2") (pin "2") (pinfunction "V+_2") (pintype "passive"))
    )
    (net (code "148") (name "unconnected-(U2-V--Pad3)") (class "Default")
      (node (ref "U2") (pin "3") (pinfunction "V-_3") (pintype "passive"))
    )
    (net (code "149") (name "unconnected-(U2-V--Pad3)_1") (class "Default")
      (node (ref "U2") (pin "3") (pinfunction "V-_3") (pintype "passive"))
    )
    (net (code "150") (name "unconnected-(U5A-Analog_In14-PadA41)") (class "Default")
      (node (ref "U5") (pin "A41") (pinfunction "Analog_In14_A41") (pintype "passive"))
    )
    (net (code "151") (name "unconnected-(U5A-Analog_In15-PadA43)") (class "Default")
      (node (ref "U5") (pin "A43") (pinfunction "Analog_In15_A43") (pintype "passive"))
    )
    (net (code "152") (name "unconnected-(U5A-BF-FPGA_TDO-PadA74)") (class "Default")
      (node (ref "U5") (pin "A74") (pinfunction "BF-FPGA_TDO_A74") (pintype "passive"))
    )
    (net (code "153") (name "unconnected-(U5A-CAN_H-PadA117)") (class "Default")
      (node (ref "U5") (pin "A117") (pinfunction "CAN_H_A117") (pintype "passive"))
    )
    (net (code "154") (name "unconnected-(U5A-CAN_L-PadA119)") (class "Default")
      (node (ref "U5") (pin "A119") (pinfunction "CAN_L_A119") (pintype "passive"))
    )
    (net (code "155") (name "unconnected-(U5A-CANnode0-PadA113)") (class "Default")
      (node (ref "U5") (pin "A113") (pinfunction "CANnode0_A113") (pintype "passive"))
    )
    (net (code "156") (name "unconnected-(U5A-CANnode1-PadA115)") (class "Default")
      (node (ref "U5") (pin "A115") (pinfunction "CANnode1_A115") (pintype "passive"))
    )
    (net (code "157") (name "unconnected-(U5A-DAC_Out1-PadA4)") (class "Default")
      (node (ref "U5") (pin "A4") (pinfunction "DAC_Out1_A4") (pintype "passive"))
    )
    (net (code "158") (name "unconnected-(U5A-DAC_Out2-PadA6)") (class "Default")
      (node (ref "U5") (pin "A6") (pinfunction "DAC_Out2_A6") (pintype "passive"))
    )
    (net (code "159") (name "unconnected-(U5A-DAC_Out3-PadA8)") (class "Default")
      (node (ref "U5") (pin "A8") (pinfunction "DAC_Out3_A8") (pintype "passive"))
    )
    (net (code "160") (name "unconnected-(U5A-DAC_Out4-PadA10)") (class "Default")
      (node (ref "U5") (pin "A10") (pinfunction "DAC_Out4_A10") (pintype "passive"))
    )
    (net (code "161") (name "unconnected-(U5A-DAC_Out5-PadA12)") (class "Default")
      (node (ref "U5") (pin "A12") (pinfunction "DAC_Out5_A12") (pintype "passive"))
    )
    (net (code "162") (name "unconnected-(U5A-DAC_Out6-PadA14)") (class "Default")
      (node (ref "U5") (pin "A14") (pinfunction "DAC_Out6_A14") (pintype "passive"))
    )
    (net (code "163") (name "unconnected-(U5A-DAC_Out7-PadA16)") (class "Default")
      (node (ref "U5") (pin "A16") (pinfunction "DAC_Out7_A16") (pintype "passive"))
    )
    (net (code "164") (name "unconnected-(U5A-EtherLED100Mbps-PadA107)") (class "Default")
      (node (ref "U5") (pin "A107") (pinfunction "EtherLED100Mbps_A107") (pintype "passive"))
    )
    (net (code "165") (name "unconnected-(U5A-FPGA_TCK-PadA78)") (class "Default")
      (node (ref "U5") (pin "A78") (pinfunction "FPGA_TCK_A78") (pintype "passive"))
    )
    (net (code "166") (name "unconnected-(U5A-FPGA_TMS-PadA76)") (class "Default")
      (node (ref "U5") (pin "A76") (pinfunction "FPGA_TMS_A76") (pintype "passive"))
    )
    (net (code "167") (name "unconnected-(U5A-GP_I{slash}Ospare14-PadA99)") (class "Default")
      (node (ref "U5") (pin "A99") (pinfunction "GP_I/Ospare14_A99") (pintype "passive"))
    )
    (net (code "168") (name "unconnected-(U5A-GP_I{slash}Ospare15-PadA101)") (class "Default")
      (node (ref "U5") (pin "A101") (pinfunction "GP_I/Ospare15_A101") (pintype "passive"))
    )
    (net (code "169") (name "unconnected-(U5A-Index1+-PadA26)") (class "Default")
      (node (ref "U5") (pin "A26") (pinfunction "Index1+_A26") (pintype "passive"))
    )
    (net (code "170") (name "unconnected-(U5A-Index1--PadA28)") (class "Default")
      (node (ref "U5") (pin "A28") (pinfunction "Index1-_A28") (pintype "passive"))
    )
    (net (code "171") (name "unconnected-(U5A-Index2+-PadA38)") (class "Default")
      (node (ref "U5") (pin "A38") (pinfunction "Index2+_A38") (pintype "passive"))
    )
    (net (code "172") (name "unconnected-(U5A-Index2--PadA40)") (class "Default")
      (node (ref "U5") (pin "A40") (pinfunction "Index2-_A40") (pintype "passive"))
    )
    (net (code "173") (name "unconnected-(U5A-Index3+-PadA50)") (class "Default")
      (node (ref "U5") (pin "A50") (pinfunction "Index3+_A50") (pintype "passive"))
    )
    (net (code "174") (name "unconnected-(U5A-Index3--PadA52)") (class "Default")
      (node (ref "U5") (pin "A52") (pinfunction "Index3-_A52") (pintype "passive"))
    )
    (net (code "175") (name "unconnected-(U5A-Index4+-PadA62)") (class "Default")
      (node (ref "U5") (pin "A62") (pinfunction "Index4+_A62") (pintype "passive"))
    )
    (net (code "176") (name "unconnected-(U5A-Index4--PadA64)") (class "Default")
      (node (ref "U5") (pin "A64") (pinfunction "Index4-_A64") (pintype "passive"))
    )
    (net (code "177") (name "unconnected-(U5A-Opto_Input24-PadA114)") (class "Default")
      (node (ref "U5") (pin "A114") (pinfunction "Opto_Input24_A114") (pintype "passive"))
    )
    (net (code "178") (name "unconnected-(U5A-Opto_Input25-PadA116)") (class "Default")
      (node (ref "U5") (pin "A116") (pinfunction "Opto_Input25_A116") (pintype "passive"))
    )
    (net (code "179") (name "unconnected-(U5A-Opto_Input26-PadA118)") (class "Default")
      (node (ref "U5") (pin "A118") (pinfunction "Opto_Input26_A118") (pintype "passive"))
    )
    (net (code "180") (name "unconnected-(U5A-Opto_Input27-PadA120)") (class "Default")
      (node (ref "U5") (pin "A120") (pinfunction "Opto_Input27_A120") (pintype "passive"))
    )
    (net (code "181") (name "unconnected-(U5A-Opto_Input_Com6-PadA112)") (class "Default")
      (node (ref "U5") (pin "A112") (pinfunction "Opto_Input_Com6_A112") (pintype "passive"))
    )
    (net (code "182") (name "unconnected-(U5A-Opto_Out_C0-PadA80)") (class "Default")
      (node (ref "U5") (pin "A80") (pinfunction "Opto_Out_C0_A80") (pintype "passive"))
    )
    (net (code "183") (name "unconnected-(U5A-Opto_Out_C1-PadA84)") (class "Default")
      (node (ref "U5") (pin "A84") (pinfunction "Opto_Out_C1_A84") (pintype "passive"))
    )
    (net (code "184") (name "unconnected-(U5A-Opto_Out_C2-PadA88)") (class "Default")
      (node (ref "U5") (pin "A88") (pinfunction "Opto_Out_C2_A88") (pintype "passive"))
    )
    (net (code "185") (name "unconnected-(U5A-Opto_Out_C3-PadA92)") (class "Default")
      (node (ref "U5") (pin "A92") (pinfunction "Opto_Out_C3_A92") (pintype "passive"))
    )
    (net (code "186") (name "unconnected-(U5A-Opto_Out_C4-PadA96)") (class "Default")
      (node (ref "U5") (pin "A96") (pinfunction "Opto_Out_C4_A96") (pintype "passive"))
    )
    (net (code "187") (name "unconnected-(U5A-Opto_Out_C5-PadA100)") (class "Default")
      (node (ref "U5") (pin "A100") (pinfunction "Opto_Out_C5_A100") (pintype "passive"))
    )
    (net (code "188") (name "unconnected-(U5A-Opto_Out_C6-PadA104)") (class "Default")
      (node (ref "U5") (pin "A104") (pinfunction "Opto_Out_C6_A104") (pintype "passive"))
    )
    (net (code "189") (name "unconnected-(U5A-Opto_Out_C7-PadA108)") (class "Default")
      (node (ref "U5") (pin "A108") (pinfunction "Opto_Out_C7_A108") (pintype "passive"))
    )
    (net (code "190") (name "unconnected-(U5A-Opto_Out_E0-PadA82)") (class "Default")
      (node (ref "U5") (pin "A82") (pinfunction "Opto_Out_E0_A82") (pintype "passive"))
    )
    (net (code "191") (name "unconnected-(U5A-Opto_Out_E1-PadA86)") (class "Default")
      (node (ref "U5") (pin "A86") (pinfunction "Opto_Out_E1_A86") (pintype "passive"))
    )
    (net (code "192") (name "unconnected-(U5A-Opto_Out_E2-PadA90)") (class "Default")
      (node (ref "U5") (pin "A90") (pinfunction "Opto_Out_E2_A90") (pintype "passive"))
    )
    (net (code "193") (name "unconnected-(U5A-Opto_Out_E3-PadA94)") (class "Default")
      (node (ref "U5") (pin "A94") (pinfunction "Opto_Out_E3_A94") (pintype "passive"))
    )
    (net (code "194") (name "unconnected-(U5A-Opto_Out_E4-PadA98)") (class "Default")
      (node (ref "U5") (pin "A98") (pinfunction "Opto_Out_E4_A98") (pintype "passive"))
    )
    (net (code "195") (name "unconnected-(U5A-Opto_Out_E5-PadA102)") (class "Default")
      (node (ref "U5") (pin "A102") (pinfunction "Opto_Out_E5_A102") (pintype "passive"))
    )
    (net (code "196") (name "unconnected-(U5A-Opto_Out_E6-PadA106)") (class "Default")
      (node (ref "U5") (pin "A106") (pinfunction "Opto_Out_E6_A106") (pintype "passive"))
    )
    (net (code "197") (name "unconnected-(U5A-Opto_Out_E7-PadA110)") (class "Default")
      (node (ref "U5") (pin "A110") (pinfunction "Opto_Out_E7_A110") (pintype "passive"))
    )
    (net (code "198") (name "unconnected-(U5A-QuadA1+-PadA18)") (class "Default")
      (node (ref "U5") (pin "A18") (pinfunction "QuadA1+_A18") (pintype "passive"))
    )
    (net (code "199") (name "unconnected-(U5A-QuadA1--PadA20)") (class "Default")
      (node (ref "U5") (pin "A20") (pinfunction "QuadA1-_A20") (pintype "passive"))
    )
    (net (code "200") (name "unconnected-(U5A-QuadA2+-PadA30)") (class "Default")
      (node (ref "U5") (pin "A30") (pinfunction "QuadA2+_A30") (pintype "passive"))
    )
    (net (code "201") (name "unconnected-(U5A-QuadA2--PadA32)") (class "Default")
      (node (ref "U5") (pin "A32") (pinfunction "QuadA2-_A32") (pintype "passive"))
    )
    (net (code "202") (name "unconnected-(U5A-QuadA3+-PadA42)") (class "Default")
      (node (ref "U5") (pin "A42") (pinfunction "QuadA3+_A42") (pintype "passive"))
    )
    (net (code "203") (name "unconnected-(U5A-QuadA3--PadA44)") (class "Default")
      (node (ref "U5") (pin "A44") (pinfunction "QuadA3-_A44") (pintype "passive"))
    )
    (net (code "204") (name "unconnected-(U5A-QuadA4+-PadA54)") (class "Default")
      (node (ref "U5") (pin "A54") (pinfunction "QuadA4+_A54") (pintype "passive"))
    )
    (net (code "205") (name "unconnected-(U5A-QuadA4--PadA56)") (class "Default")
      (node (ref "U5") (pin "A56") (pinfunction "QuadA4-_A56") (pintype "passive"))
    )
    (net (code "206") (name "unconnected-(U5A-QuadB1+-PadA22)") (class "Default")
      (node (ref "U5") (pin "A22") (pinfunction "QuadB1+_A22") (pintype "passive"))
    )
    (net (code "207") (name "unconnected-(U5A-QuadB1--PadA24)") (class "Default")
      (node (ref "U5") (pin "A24") (pinfunction "QuadB1-_A24") (pintype "passive"))
    )
    (net (code "208") (name "unconnected-(U5A-QuadB2+-PadA34)") (class "Default")
      (node (ref "U5") (pin "A34") (pinfunction "QuadB2+_A34") (pintype "passive"))
    )
    (net (code "209") (name "unconnected-(U5A-QuadB2--PadA36)") (class "Default")
      (node (ref "U5") (pin "A36") (pinfunction "QuadB2-_A36") (pintype "passive"))
    )
    (net (code "210") (name "unconnected-(U5A-QuadB3+-PadA46)") (class "Default")
      (node (ref "U5") (pin "A46") (pinfunction "QuadB3+_A46") (pintype "passive"))
    )
    (net (code "211") (name "unconnected-(U5A-QuadB3--PadA48)") (class "Default")
      (node (ref "U5") (pin "A48") (pinfunction "QuadB3-_A48") (pintype "passive"))
    )
    (net (code "212") (name "unconnected-(U5A-QuadB4+-PadA58)") (class "Default")
      (node (ref "U5") (pin "A58") (pinfunction "QuadB4+_A58") (pintype "passive"))
    )
    (net (code "213") (name "unconnected-(U5A-QuadB4--PadA60)") (class "Default")
      (node (ref "U5") (pin "A60") (pinfunction "QuadB4-_A60") (pintype "passive"))
    )
    (net (code "214") (name "unconnected-(U5A-RS485_H-PadA57)") (class "Default")
      (node (ref "U5") (pin "A57") (pinfunction "RS485_H_A57") (pintype "passive"))
    )
    (net (code "215") (name "unconnected-(U5A-RS485_L-PadA59)") (class "Default")
      (node (ref "U5") (pin "A59") (pinfunction "RS485_L_A59") (pintype "passive"))
    )
    (net (code "216") (name "unconnected-(U5A-SPI_MISO-PadA65)") (class "Default")
      (node (ref "U5") (pin "A65") (pinfunction "SPI_MISO_A65") (pintype "passive"))
    )
    (net (code "217") (name "unconnected-(U5A-SPI_MOSI-PadA63)") (class "Default")
      (node (ref "U5") (pin "A63") (pinfunction "SPI_MOSI_A63") (pintype "passive"))
    )
    (net (code "218") (name "unconnected-(U5A-SPI_SClk-PadA61)") (class "Default")
      (node (ref "U5") (pin "A61") (pinfunction "SPI_SClk_A61") (pintype "passive"))
    )
    (net (code "219") (name "unconnected-(U5A-SPI_SS-PadA67)") (class "Default")
      (node (ref "U5") (pin "A67") (pinfunction "SPI_SS_A67") (pintype "passive"))
    )
    (net (code "220") (name "unconnected-(U5A-SPI_SSEL1-PadA69)") (class "Default")
      (node (ref "U5") (pin "A69") (pinfunction "SPI_SSEL1_A69") (pintype "passive"))
    )
    (net (code "221") (name "unconnected-(U5A-TDO-App_TDI-PadA72)") (class "Default")
      (node (ref "U5") (pin "A72") (pinfunction "TDO-App_TDI_A72") (pintype "passive"))
    )
    (net (code "222") (name "unconnected-(U5B-Direction1-PadB39)") (class "Default")
      (node (ref "U5") (pin "B39") (pinfunction "Direction1_B39") (pintype "passive"))
    )
    (net (code "223") (name "unconnected-(U5B-Direction2-PadB41)") (class "Default")
      (node (ref "U5") (pin "B41") (pinfunction "Direction2_B41") (pintype "passive"))
    )
    (net (code "224") (name "unconnected-(U5B-Direction3-PadB43)") (class "Default")
      (node (ref "U5") (pin "B43") (pinfunction "Direction3_B43") (pintype "passive"))
    )
    (net (code "225") (name "unconnected-(U5B-Direction4-PadB45)") (class "Default")
      (node (ref "U5") (pin "B45") (pinfunction "Direction4_B45") (pintype "passive"))
    )
    (net (code "226") (name "unconnected-(U5B-EtherGND-PadB69)") (class "Default")
      (node (ref "U5") (pin "B69") (pinfunction "EtherGND_B69") (pintype "passive"))
    )
    (net (code "227") (name "unconnected-(U5B-GP_Out_D24-PadB90)") (class "Default")
      (node (ref "U5") (pin "B90") (pinfunction "GP_Out_D24_B90") (pintype "passive"))
    )
    (net (code "228") (name "unconnected-(U5B-GP_Out_D25-PadB94)") (class "Default")
      (node (ref "U5") (pin "B94") (pinfunction "GP_Out_D25_B94") (pintype "passive"))
    )
    (net (code "229") (name "unconnected-(U5B-GP_Out_D26-PadB98)") (class "Default")
      (node (ref "U5") (pin "B98") (pinfunction "GP_Out_D26_B98") (pintype "passive"))
    )
    (net (code "230") (name "unconnected-(U5B-GP_Out_D27-PadB102)") (class "Default")
      (node (ref "U5") (pin "B102") (pinfunction "GP_Out_D27_B102") (pintype "passive"))
    )
    (net (code "231") (name "unconnected-(U5B-GP_Out_D28-PadB106)") (class "Default")
      (node (ref "U5") (pin "B106") (pinfunction "GP_Out_D28_B106") (pintype "passive"))
    )
    (net (code "232") (name "unconnected-(U5B-GP_Out_D29-PadB110)") (class "Default")
      (node (ref "U5") (pin "B110") (pinfunction "GP_Out_D29_B110") (pintype "passive"))
    )
    (net (code "233") (name "unconnected-(U5B-GP_Out_D30-PadB114)") (class "Default")
      (node (ref "U5") (pin "B114") (pinfunction "GP_Out_D30_B114") (pintype "passive"))
    )
    (net (code "234") (name "unconnected-(U5B-GP_Out_D31-PadB118)") (class "Default")
      (node (ref "U5") (pin "B118") (pinfunction "GP_Out_D31_B118") (pintype "passive"))
    )
    (net (code "235") (name "unconnected-(U5B-GP_Out_S24-PadB92)") (class "Default")
      (node (ref "U5") (pin "B92") (pinfunction "GP_Out_S24_B92") (pintype "passive"))
    )
    (net (code "236") (name "unconnected-(U5B-GP_Out_S25-PadB96)") (class "Default")
      (node (ref "U5") (pin "B96") (pinfunction "GP_Out_S25_B96") (pintype "passive"))
    )
    (net (code "237") (name "unconnected-(U5B-GP_Out_S26-PadB100)") (class "Default")
      (node (ref "U5") (pin "B100") (pinfunction "GP_Out_S26_B100") (pintype "passive"))
    )
    (net (code "238") (name "unconnected-(U5B-GP_Out_S27-PadB104)") (class "Default")
      (node (ref "U5") (pin "B104") (pinfunction "GP_Out_S27_B104") (pintype "passive"))
    )
    (net (code "239") (name "unconnected-(U5B-GP_Out_S28-PadB108)") (class "Default")
      (node (ref "U5") (pin "B108") (pinfunction "GP_Out_S28_B108") (pintype "passive"))
    )
    (net (code "240") (name "unconnected-(U5B-GP_Out_S29-PadB112)") (class "Default")
      (node (ref "U5") (pin "B112") (pinfunction "GP_Out_S29_B112") (pintype "passive"))
    )
    (net (code "241") (name "unconnected-(U5B-GP_Out_S30-PadB116)") (class "Default")
      (node (ref "U5") (pin "B116") (pinfunction "GP_Out_S30_B116") (pintype "passive"))
    )
    (net (code "242") (name "unconnected-(U5B-GP_Out_S31-PadB120)") (class "Default")
      (node (ref "U5") (pin "B120") (pinfunction "GP_Out_S31_B120") (pintype "passive"))
    )
    (net (code "243") (name "unconnected-(U5B-HomeCom-PadB9)") (class "Default")
      (node (ref "U5") (pin "B9") (pinfunction "HomeCom_B9") (pintype "passive"))
    )
    (net (code "244") (name "unconnected-(U5B-NegLimt1-PadB27)") (class "Default")
      (node (ref "U5") (pin "B27") (pinfunction "NegLimt1_B27") (pintype "passive"))
    )
    (net (code "245") (name "unconnected-(U5B-NegLimt2-PadB25)") (class "Default")
      (node (ref "U5") (pin "B25") (pinfunction "NegLimt2_B25") (pintype "passive"))
    )
    (net (code "246") (name "unconnected-(U5B-NegLimt3-PadB23)") (class "Default")
      (node (ref "U5") (pin "B23") (pinfunction "NegLimt3_B23") (pintype "passive"))
    )
    (net (code "247") (name "unconnected-(U5B-NegLimt4-PadB21)") (class "Default")
      (node (ref "U5") (pin "B21") (pinfunction "NegLimt4_B21") (pintype "passive"))
    )
    (net (code "248") (name "unconnected-(U5B-NegLimtCom-PadB29)") (class "Default")
      (node (ref "U5") (pin "B29") (pinfunction "NegLimtCom_B29") (pintype "passive"))
    )
    (net (code "249") (name "unconnected-(U5B-Opto_Input13-PadB95)") (class "Default")
      (node (ref "U5") (pin "B95") (pinfunction "Opto_Input13_B95") (pintype "passive"))
    )
    (net (code "250") (name "unconnected-(U5B-Opto_Input14-PadB97)") (class "Default")
      (node (ref "U5") (pin "B97") (pinfunction "Opto_Input14_B97") (pintype "passive"))
    )
    (net (code "251") (name "unconnected-(U5B-Opto_Input15-PadB99)") (class "Default")
      (node (ref "U5") (pin "B99") (pinfunction "Opto_Input15_B99") (pintype "passive"))
    )
    (net (code "252") (name "unconnected-(U5B-Opto_Input16-PadB103)") (class "Default")
      (node (ref "U5") (pin "B103") (pinfunction "Opto_Input16_B103") (pintype "passive"))
    )
    (net (code "253") (name "unconnected-(U5B-Opto_Input17-PadB105)") (class "Default")
      (node (ref "U5") (pin "B105") (pinfunction "Opto_Input17_B105") (pintype "passive"))
    )
    (net (code "254") (name "unconnected-(U5B-Opto_Input18-PadB107)") (class "Default")
      (node (ref "U5") (pin "B107") (pinfunction "Opto_Input18_B107") (pintype "passive"))
    )
    (net (code "255") (name "unconnected-(U5B-Opto_Input19-PadB109)") (class "Default")
      (node (ref "U5") (pin "B109") (pinfunction "Opto_Input19_B109") (pintype "passive"))
    )
    (net (code "256") (name "unconnected-(U5B-Opto_Input20-PadB113)") (class "Default")
      (node (ref "U5") (pin "B113") (pinfunction "Opto_Input20_B113") (pintype "passive"))
    )
    (net (code "257") (name "unconnected-(U5B-Opto_Input21-PadB115)") (class "Default")
      (node (ref "U5") (pin "B115") (pinfunction "Opto_Input21_B115") (pintype "passive"))
    )
    (net (code "258") (name "unconnected-(U5B-Opto_Input22-PadB117)") (class "Default")
      (node (ref "U5") (pin "B117") (pinfunction "Opto_Input22_B117") (pintype "passive"))
    )
    (net (code "259") (name "unconnected-(U5B-Opto_Input23-PadB119)") (class "Default")
      (node (ref "U5") (pin "B119") (pinfunction "Opto_Input23_B119") (pintype "passive"))
    )
    (net (code "260") (name "unconnected-(U5B-Opto_Input_Com4-PadB101)") (class "Default")
      (node (ref "U5") (pin "B101") (pinfunction "Opto_Input_Com4_B101") (pintype "passive"))
    )
    (net (code "261") (name "unconnected-(U5B-Opto_Input_Com5-PadB111)") (class "Default")
      (node (ref "U5") (pin "B111") (pinfunction "Opto_Input_Com5_B111") (pintype "passive"))
    )
    (net (code "262") (name "unconnected-(U5B-PosLimt1-PadB17)") (class "Default")
      (node (ref "U5") (pin "B17") (pinfunction "PosLimt1_B17") (pintype "passive"))
    )
    (net (code "263") (name "unconnected-(U5B-PosLimt2-PadB15)") (class "Default")
      (node (ref "U5") (pin "B15") (pinfunction "PosLimt2_B15") (pintype "passive"))
    )
    (net (code "264") (name "unconnected-(U5B-PosLimt3-PadB13)") (class "Default")
      (node (ref "U5") (pin "B13") (pinfunction "PosLimt3_B13") (pintype "passive"))
    )
    (net (code "265") (name "unconnected-(U5B-PosLimt4-PadB11)") (class "Default")
      (node (ref "U5") (pin "B11") (pinfunction "PosLimt4_B11") (pintype "passive"))
    )
    (net (code "266") (name "unconnected-(U5B-PosLimtCom-PadB19)") (class "Default")
      (node (ref "U5") (pin "B19") (pinfunction "PosLimtCom_B19") (pintype "passive"))
    )
    (net (code "267") (name "unconnected-(U5B-Step1-PadB31)") (class "Default")
      (node (ref "U5") (pin "B31") (pinfunction "Step1_B31") (pintype "passive"))
    )
    (net (code "268") (name "unconnected-(U5B-Step2-PadB33)") (class "Default")
      (node (ref "U5") (pin "B33") (pinfunction "Step2_B33") (pintype "passive"))
    )
    (net (code "269") (name "unconnected-(U5B-Step3-PadB35)") (class "Default")
      (node (ref "U5") (pin "B35") (pinfunction "Step3_B35") (pintype "passive"))
    )
    (net (code "270") (name "unconnected-(U5B-Step4-PadB37)") (class "Default")
      (node (ref "U5") (pin "B37") (pinfunction "Step4_B37") (pintype "passive"))
    )
    (net (code "271") (name "unconnected-(U5B-~Home1-PadB7)") (class "Default")
      (node (ref "U5") (pin "B7") (pinfunction "~Home1_B7") (pintype "passive"))
    )
    (net (code "272") (name "unconnected-(U5B-~Home2-PadB5)") (class "Default")
      (node (ref "U5") (pin "B5") (pinfunction "~Home2_B5") (pintype "passive"))
    )
    (net (code "273") (name "unconnected-(U5B-~Home3-PadB3)") (class "Default")
      (node (ref "U5") (pin "B3") (pinfunction "~Home3_B3") (pintype "passive"))
    )
    (net (code "274") (name "unconnected-(U5B-~Home4-PadB1)") (class "Default")
      (node (ref "U5") (pin "B1") (pinfunction "~Home4_B1") (pintype "passive"))
    )
    (net (code "275") (name "unconnected-(U6-NC-Pad5)") (class "Default")
      (node (ref "U6") (pin "5") (pinfunction "NC_5") (pintype "passive"))
    )
    (net (code "276") (name "unconnected-(U6-VOSTRIM-Pad1)") (class "Default")
      (node (ref "U6") (pin "1") (pinfunction "VOSTRIM_1") (pintype "passive"))
    )
    (net (code "277") (name "unconnected-(U6-VOSTRIM-Pad8)") (class "Default")
      (node (ref "U6") (pin "8") (pinfunction "VOSTRIM_8") (pintype "passive"))
    )
  )
)
